# BuckDC_33.net
KiCad netlist of a schematic drawn in Altium Designer
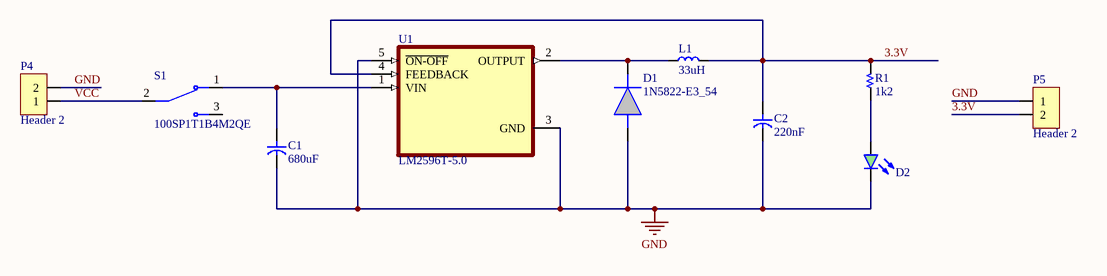
[diagram p0: BuckDC_33.SchDoc]

(export (version "E")
  (design (tool "Eeschema 10.0.6"))
  (components
    (comp (ref "C1")
      (value "680uF")
      (footprint "CAP/D80/H125/LS35")
      (description "Capacitor pol")
      (libsource (lib "chipfc_altium_libs") (part "Capacitor"))
    )
    (comp (ref "C2")
      (value "220nF")
      (footprint "CAP/D80/H125/LS35")
      (description "Capacitor pol")
      (libsource (lib "chipfc_altium_libs") (part "Capacitor"))
    )
    (comp (ref "D1")
      (value "1N5822-E3_54")
      (footprint "DIOAD2855W132L835D505")
      (description "VISHAY - 1N5822-E3/54 - Schottky Rectifier, 40 V, 3 A, Single, DO-201AD, 2 Pins, 525 mV")
      (fields
        (field (name "MANUFACTURER_PART_NUMBER") "1N5822-E3/54")
        (field (name "MOUSER PART NUMBER") "625-1N5822-E3")
      )
      (libsource (lib "1N5822-E3_54") (part "1N5822-E3_54"))
    )
    (comp (ref "D2")
      (value "LED GREEN")
      (footprint "LED 10MM - GREEN")
      (description "Typical LED 3-pin 2-color")
      (libsource (lib "chipfc_altium_libs") (part "LED GREEN"))
    )
    (comp (ref "L1")
      (value "33uH")
      (footprint "R 1/4W")
      (description "Inductor")
      (libsource (lib "chipfc_altium_libs") (part "Inductor"))
    )
    (comp (ref "P4")
      (value "Header 2")
      (footprint "HDR/Terminal/2")
      (description "Header, 2-Pin")
      (libsource (lib "") (part "Header 2_1"))
    )
    (comp (ref "P5")
      (value "Header 2")
      (footprint "HDR/Terminal/2")
      (description "Header, 2-Pin")
      (libsource (lib "chipfc_altium_libs") (part "Header 2"))
    )
    (comp (ref "R1")
      (value "1k2")
      (footprint "R 1/4W/300")
      (description "Resistor")
      (libsource (lib "chipfc_altium_libs") (part "Resistor"))
    )
    (comp (ref "S1")
      (value "100SP1T1B4M2QE")
      (footprint "SW_100SP1T1B4M2QE")
      (description "Toggle Switch SPDT Through Hole")
      (libsource (lib "100SP1T1B4M2QE") (part "100SP1T1B4M2QE"))
    )
    (comp (ref "U1")
      (value "LM2596T-5.0")
      (footprint "TO170P1016X470X2092-5")
      (description "SIMPLE SWITCHERÂ® 4.5V to 40V, 3A Low Component Count Step-Down Regulator 5-TO-220")
      (fields (field (name "MF") "Texas Instruments"))
      (libsource (lib "LM2596T-5.0") (part "LM2596T-5.0"))
    )
  )
  (nets
    (net (code "1") (name "/3.3V") (class "Default")
      (node (ref "C2") (pin "1") (pinfunction "1_1") (pintype "passive"))
      (node (ref "L1") (pin "2") (pinfunction "2_2") (pintype "passive"))
      (node (ref "P5") (pin "2") (pinfunction "2_2") (pintype "passive"))
      (node (ref "R1") (pin "2") (pinfunction "2_2") (pintype "passive"))
      (node (ref "U1") (pin "4") (pinfunction "FEEDBACK_4") (pintype "input"))
    )
    (net (code "2") (name "/VCC") (class "Default")
      (node (ref "P4") (pin "1") (pinfunction "1_1") (pintype "passive"))
      (node (ref "S1") (pin "2") (pinfunction "2_2") (pintype "passive"))
    )
    (net (code "3") (name "GND") (class "Default")
      (node (ref "C1") (pin "2") (pinfunction "2_2") (pintype "passive"))
      (node (ref "C2") (pin "2") (pinfunction "2_2") (pintype "passive"))
      (node (ref "D1") (pin "1") (pinfunction "A_1") (pintype "passive"))
      (node (ref "D2") (pin "2") (pinfunction "K_2") (pintype "passive"))
      (node (ref "P4") (pin "2") (pinfunction "2_2") (pintype "passive"))
      (node (ref "P5") (pin "1") (pinfunction "1_1") (pintype "passive"))
      (node (ref "U1") (pin "3") (pinfunction "GND_3") (pintype "power_in"))
      (node (ref "U1") (pin "5") (pinfunction "~{ON-OFF}_5") (pintype "input"))
    )
    (net (code "4") (name "Net-(D1-K)") (class "Default")
      (node (ref "D1") (pin "2") (pinfunction "K_2") (pintype "passive"))
      (node (ref "L1") (pin "1") (pinfunction "1_1") (pintype "passive"))
      (node (ref "U1") (pin "2") (pinfunction "OUTPUT_2") (pintype "output"))
    )
    (net (code "5") (name "Net-(D2-A)") (class "Default")
      (node (ref "D2") (pin "1") (pinfunction "A_1") (pintype "passive"))
      (node (ref "R1") (pin "1") (pinfunction "1_1") (pintype "passive"))
    )
    (net (code "6") (name "Net-(U1-VIN)") (class "Default")
      (node (ref "C1") (pin "1") (pinfunction "1_1") (pintype "passive"))
      (node (ref "S1") (pin "1") (pinfunction "1_1") (pintype "passive"))
      (node (ref "U1") (pin "1") (pinfunction "VIN_1") (pintype "input"))
    )
    (net (code "7") (name "unconnected-(S1-Pad3)") (class "Default")
      (node (ref "S1") (pin "3") (pinfunction "3_3") (pintype "passive"))
    )
  )
)
